# flipdotctl.net
KiCad netlist of a schematic drawn in EAGLE
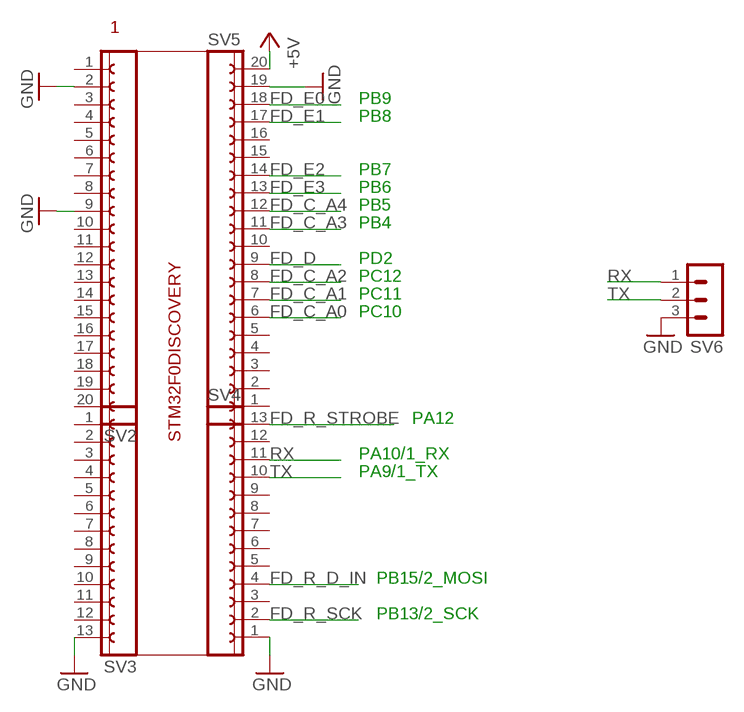
[diagram p0: schematic, sheet 1]
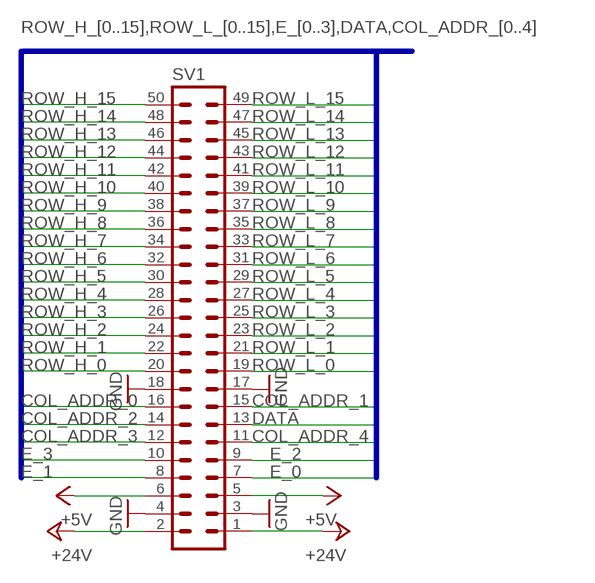
[diagram p1: schematic, sheet 2]
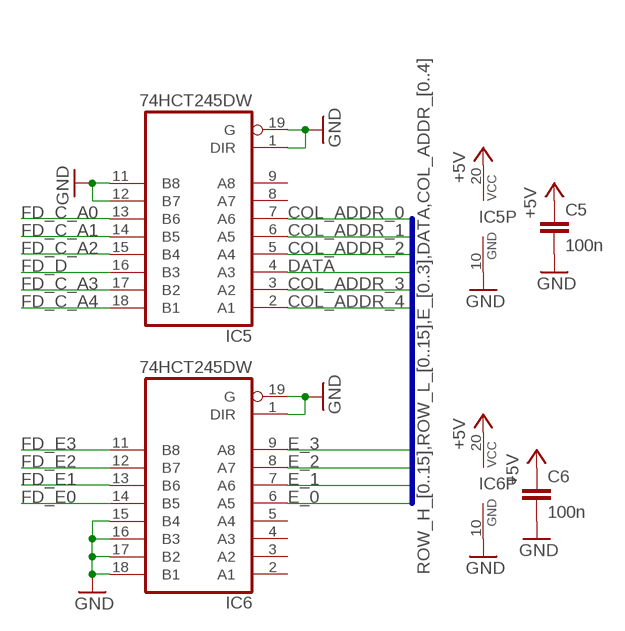
[diagram p2: schematic, sheet 3]
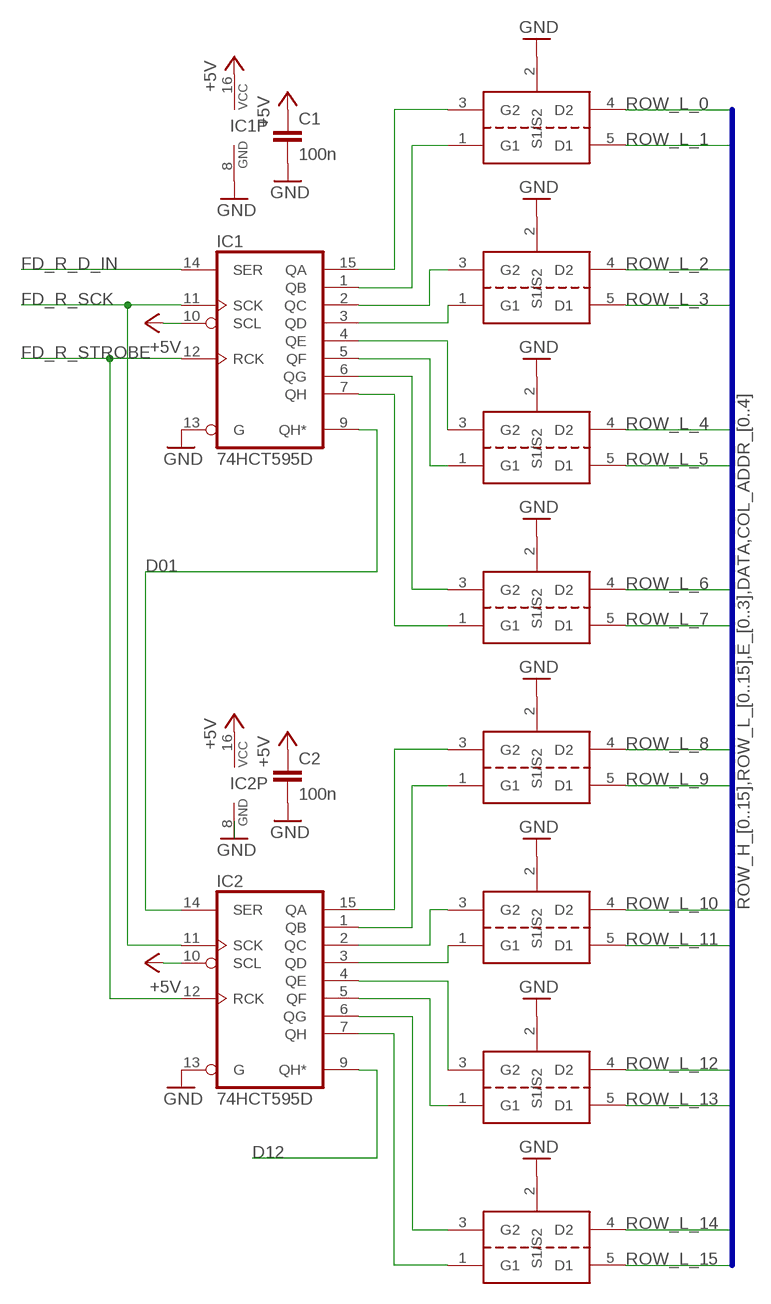
[diagram p3: schematic, sheet 4]
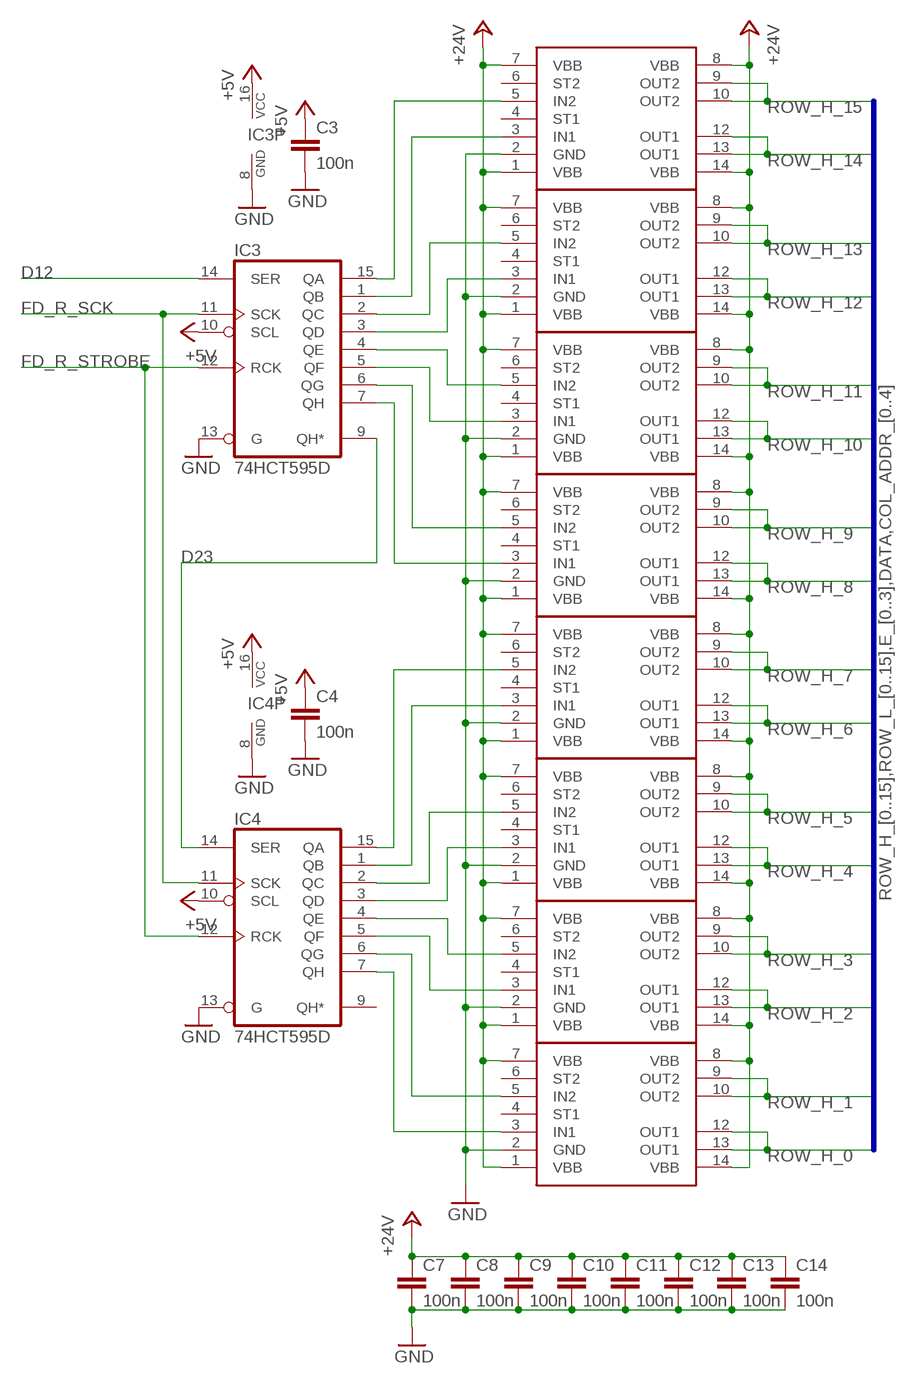
[diagram p4: schematic, sheet 5]
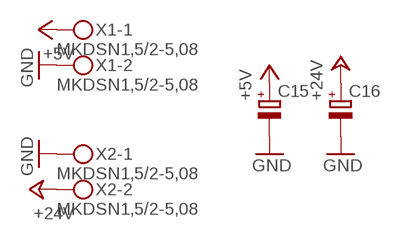
[diagram p5: schematic, sheet 6]

(export (version "E")
  (design (tool "Eeschema 10.0.6"))
  (components
    (comp (ref "C3")
      (value "100n")
      (footprint "eagle-import:C0603")
      (libsource (lib "eagle-import") (part "C-EUC0603"))
    )
    (comp (ref "C4")
      (value "100n")
      (footprint "eagle-import:C0603")
      (libsource (lib "eagle-import") (part "C-EUC0603"))
    )
    (comp (ref "C7")
      (value "100n")
      (footprint "eagle-import:C0603")
      (libsource (lib "eagle-import") (part "C-EUC0603"))
    )
    (comp (ref "C8")
      (value "100n")
      (footprint "eagle-import:C0603")
      (libsource (lib "eagle-import") (part "C-EUC0603"))
    )
    (comp (ref "C9")
      (value "100n")
      (footprint "eagle-import:C0603")
      (libsource (lib "eagle-import") (part "C-EUC0603"))
    )
    (comp (ref "C10")
      (value "100n")
      (footprint "eagle-import:C0603")
      (libsource (lib "eagle-import") (part "C-EUC0603"))
    )
    (comp (ref "C11")
      (value "100n")
      (footprint "eagle-import:C0603")
      (libsource (lib "eagle-import") (part "C-EUC0603"))
    )
    (comp (ref "C12")
      (value "100n")
      (footprint "eagle-import:C0603")
      (libsource (lib "eagle-import") (part "C-EUC0603"))
    )
    (comp (ref "C13")
      (value "100n")
      (footprint "eagle-import:C0603")
      (libsource (lib "eagle-import") (part "C-EUC0603"))
    )
    (comp (ref "C14")
      (value "100n")
      (footprint "eagle-import:C0603")
      (libsource (lib "eagle-import") (part "C-EUC0603"))
    )
    (comp (ref "IC3")
      (value "74HCT595D")
      (footprint "eagle-import:SO16")
      (libsource (lib "eagle-import") (part "74595DHCT"))
    )
    (comp (ref "IC4")
      (value "74HCT595D")
      (footprint "eagle-import:SO16")
      (libsource (lib "eagle-import") (part "74595DHCT"))
    )
    (comp (ref "U$9")
      (value "BTS5210G")
      (footprint "eagle-import:SO-14")
      (libsource (lib "eagle-import") (part "BTS5210G"))
    )
    (comp (ref "U$10")
      (value "BTS5210G")
      (footprint "eagle-import:SO-14")
      (libsource (lib "eagle-import") (part "BTS5210G"))
    )
    (comp (ref "U$11")
      (value "BTS5210G")
      (footprint "eagle-import:SO-14")
      (libsource (lib "eagle-import") (part "BTS5210G"))
    )
    (comp (ref "U$12")
      (value "BTS5210G")
      (footprint "eagle-import:SO-14")
      (libsource (lib "eagle-import") (part "BTS5210G"))
    )
    (comp (ref "U$13")
      (value "BTS5210G")
      (footprint "eagle-import:SO-14")
      (libsource (lib "eagle-import") (part "BTS5210G"))
    )
    (comp (ref "U$14")
      (value "BTS5210G")
      (footprint "eagle-import:SO-14")
      (libsource (lib "eagle-import") (part "BTS5210G"))
    )
    (comp (ref "U$15")
      (value "BTS5210G")
      (footprint "eagle-import:SO-14")
      (libsource (lib "eagle-import") (part "BTS5210G"))
    )
    (comp (ref "U$16")
      (value "BTS5210G")
      (footprint "eagle-import:SO-14")
      (libsource (lib "eagle-import") (part "BTS5210G"))
    )
    (comp (ref "SV2")
      (value "FE20-1")
      (footprint "eagle-import:FE20")
      (libsource (lib "eagle-import") (part "FE20-1"))
    )
    (comp (ref "SV3")
      (value "FE13-1")
      (footprint "eagle-import:FE13")
      (libsource (lib "eagle-import") (part "FE13-1"))
    )
    (comp (ref "SV4")
      (value "FE13-1")
      (footprint "eagle-import:FE13")
      (libsource (lib "eagle-import") (part "FE13-1"))
    )
    (comp (ref "SV5")
      (value "FE20-1")
      (footprint "eagle-import:FE20")
      (libsource (lib "eagle-import") (part "FE20-1"))
    )
    (comp (ref "SV6")
      (value "MA03-1")
      (footprint "eagle-import:MA03-1")
      (libsource (lib "eagle-import") (part "MA03-1"))
    )
    (comp (ref "C1")
      (value "100n")
      (footprint "eagle-import:C0603")
      (libsource (lib "eagle-import") (part "C-EUC0603"))
    )
    (comp (ref "C2")
      (value "100n")
      (footprint "eagle-import:C0603")
      (libsource (lib "eagle-import") (part "C-EUC0603"))
    )
    (comp (ref "IC1")
      (value "74HCT595D")
      (footprint "eagle-import:SO16")
      (libsource (lib "eagle-import") (part "74595DHCT"))
    )
    (comp (ref "IC2")
      (value "74HCT595D")
      (footprint "eagle-import:SO16")
      (libsource (lib "eagle-import") (part "74595DHCT"))
    )
    (comp (ref "U$1")
      (value "QS5K2")
      (footprint "eagle-import:SOT23-5L")
      (libsource (lib "eagle-import") (part "QS5K2"))
    )
    (comp (ref "U$2")
      (value "QS5K2")
      (footprint "eagle-import:SOT23-5L")
      (libsource (lib "eagle-import") (part "QS5K2"))
    )
    (comp (ref "U$3")
      (value "QS5K2")
      (footprint "eagle-import:SOT23-5L")
      (libsource (lib "eagle-import") (part "QS5K2"))
    )
    (comp (ref "U$4")
      (value "QS5K2")
      (footprint "eagle-import:SOT23-5L")
      (libsource (lib "eagle-import") (part "QS5K2"))
    )
    (comp (ref "U$5")
      (value "QS5K2")
      (footprint "eagle-import:SOT23-5L")
      (libsource (lib "eagle-import") (part "QS5K2"))
    )
    (comp (ref "U$6")
      (value "QS5K2")
      (footprint "eagle-import:SOT23-5L")
      (libsource (lib "eagle-import") (part "QS5K2"))
    )
    (comp (ref "U$7")
      (value "QS5K2")
      (footprint "eagle-import:SOT23-5L")
      (libsource (lib "eagle-import") (part "QS5K2"))
    )
    (comp (ref "U$8")
      (value "QS5K2")
      (footprint "eagle-import:SOT23-5L")
      (libsource (lib "eagle-import") (part "QS5K2"))
    )
    (comp (ref "SV1")
      (value "ML50")
      (footprint "eagle-import:ML50")
      (libsource (lib "eagle-import") (part "ML50"))
    )
    (comp (ref "C15")
      (value "CPOL-EUE2.5-6")
      (footprint "eagle-import:E2,5-6")
      (libsource (lib "eagle-import") (part "CPOL-EUE2.5-6"))
    )
    (comp (ref "C16")
      (value "CPOL-EUE2.5-6")
      (footprint "eagle-import:E2,5-6")
      (libsource (lib "eagle-import") (part "CPOL-EUE2.5-6"))
    )
    (comp (ref "X1")
      (value "MKDSN1,5/2-5,08")
      (footprint "eagle-import:MKDSN1,5_2-5,08")
      (fields (field (name "MPN") "MKDSN 1,5/2-5.08"))
      (libsource (lib "eagle-import") (part "MKDSN1,5/2-5,08"))
    )
    (comp (ref "X2")
      (value "MKDSN1,5/2-5,08")
      (footprint "eagle-import:MKDSN1,5_2-5,08")
      (fields (field (name "MPN") "MKDSN 1,5/2-5.08"))
      (libsource (lib "eagle-import") (part "MKDSN1,5/2-5,08"))
    )
    (comp (ref "C5")
      (value "100n")
      (footprint "eagle-import:C0603")
      (libsource (lib "eagle-import") (part "C-EUC0603"))
    )
    (comp (ref "C6")
      (value "100n")
      (footprint "eagle-import:C0603")
      (libsource (lib "eagle-import") (part "C-EUC0603"))
    )
    (comp (ref "IC5")
      (value "74HCT245DW")
      (footprint "eagle-import:SO20W")
      (libsource (lib "eagle-import") (part "74245DWHCT"))
    )
    (comp (ref "IC6")
      (value "74HCT245DW")
      (footprint "eagle-import:SO20W")
      (libsource (lib "eagle-import") (part "74245DWHCT"))
    )
  )
  (nets
    (net (code "3") (name "+5V") (class "Default")
      (node (ref "C1") (pin "1") (pinfunction "1_1") (pintype "passive"))
      (node (ref "C15") (pin "+") (pinfunction "+_+") (pintype "passive"))
      (node (ref "C2") (pin "1") (pinfunction "1_1") (pintype "passive"))
      (node (ref "C3") (pin "1") (pinfunction "1_1") (pintype "passive"))
      (node (ref "C4") (pin "1") (pinfunction "1_1") (pintype "passive"))
      (node (ref "C5") (pin "1") (pinfunction "1_1") (pintype "passive"))
      (node (ref "C6") (pin "1") (pinfunction "1_1") (pintype "passive"))
      (node (ref "IC1") (pin "10") (pinfunction "SCL_10") (pintype "input"))
      (node (ref "IC1") (pin "16") (pinfunction "VCC_16") (pintype "power_in"))
      (node (ref "IC2") (pin "10") (pinfunction "SCL_10") (pintype "input"))
      (node (ref "IC2") (pin "16") (pinfunction "VCC_16") (pintype "power_in"))
      (node (ref "IC3") (pin "10") (pinfunction "SCL_10") (pintype "input"))
      (node (ref "IC3") (pin "16") (pinfunction "VCC_16") (pintype "power_in"))
      (node (ref "IC4") (pin "10") (pinfunction "SCL_10") (pintype "input"))
      (node (ref "IC4") (pin "16") (pinfunction "VCC_16") (pintype "power_in"))
      (node (ref "IC5") (pin "20") (pinfunction "VCC_20") (pintype "power_in"))
      (node (ref "IC6") (pin "20") (pinfunction "VCC_20") (pintype "power_in"))
      (node (ref "SV1") (pin "5") (pinfunction "5_5") (pintype "passive"))
      (node (ref "SV1") (pin "6") (pinfunction "6_6") (pintype "passive"))
      (node (ref "SV5") (pin "20") (pinfunction "20_20") (pintype "passive"))
      (node (ref "X1") (pin "1") (pinfunction "KL_1") (pintype "passive"))
    )
    (net (code "4") (name "+24V") (class "Default")
      (node (ref "C10") (pin "1") (pinfunction "1_1") (pintype "passive"))
      (node (ref "C11") (pin "1") (pinfunction "1_1") (pintype "passive"))
      (node (ref "C12") (pin "1") (pinfunction "1_1") (pintype "passive"))
      (node (ref "C13") (pin "1") (pinfunction "1_1") (pintype "passive"))
      (node (ref "C14") (pin "1") (pinfunction "1_1") (pintype "passive"))
      (node (ref "C16") (pin "+") (pinfunction "+_+") (pintype "passive"))
      (node (ref "C7") (pin "1") (pinfunction "1_1") (pintype "passive"))
      (node (ref "C8") (pin "1") (pinfunction "1_1") (pintype "passive"))
      (node (ref "C9") (pin "1") (pinfunction "1_1") (pintype "passive"))
      (node (ref "SV1") (pin "1") (pinfunction "1_1") (pintype "passive"))
      (node (ref "SV1") (pin "2") (pinfunction "2_2") (pintype "passive"))
      (node (ref "U$10") (pin "1") (pinfunction "VBB_1") (pintype "bidirectional"))
      (node (ref "U$10") (pin "14") (pinfunction "VBB_14") (pintype "bidirectional"))
      (node (ref "U$10") (pin "7") (pinfunction "VBB_7") (pintype "bidirectional"))
      (node (ref "U$10") (pin "8") (pinfunction "VBB_8") (pintype "bidirectional"))
      (node (ref "U$11") (pin "1") (pinfunction "VBB_1") (pintype "bidirectional"))
      (node (ref "U$11") (pin "14") (pinfunction "VBB_14") (pintype "bidirectional"))
      (node (ref "U$11") (pin "7") (pinfunction "VBB_7") (pintype "bidirectional"))
      (node (ref "U$11") (pin "8") (pinfunction "VBB_8") (pintype "bidirectional"))
      (node (ref "U$12") (pin "1") (pinfunction "VBB_1") (pintype "bidirectional"))
      (node (ref "U$12") (pin "14") (pinfunction "VBB_14") (pintype "bidirectional"))
      (node (ref "U$12") (pin "7") (pinfunction "VBB_7") (pintype "bidirectional"))
      (node (ref "U$12") (pin "8") (pinfunction "VBB_8") (pintype "bidirectional"))
      (node (ref "U$13") (pin "1") (pinfunction "VBB_1") (pintype "bidirectional"))
      (node (ref "U$13") (pin "14") (pinfunction "VBB_14") (pintype "bidirectional"))
      (node (ref "U$13") (pin "7") (pinfunction "VBB_7") (pintype "bidirectional"))
      (node (ref "U$13") (pin "8") (pinfunction "VBB_8") (pintype "bidirectional"))
      (node (ref "U$14") (pin "1") (pinfunction "VBB_1") (pintype "bidirectional"))
      (node (ref "U$14") (pin "14") (pinfunction "VBB_14") (pintype "bidirectional"))
      (node (ref "U$14") (pin "7") (pinfunction "VBB_7") (pintype "bidirectional"))
      (node (ref "U$14") (pin "8") (pinfunction "VBB_8") (pintype "bidirectional"))
      (node (ref "U$15") (pin "1") (pinfunction "VBB_1") (pintype "bidirectional"))
      (node (ref "U$15") (pin "14") (pinfunction "VBB_14") (pintype "bidirectional"))
      (node (ref "U$15") (pin "7") (pinfunction "VBB_7") (pintype "bidirectional"))
      (node (ref "U$15") (pin "8") (pinfunction "VBB_8") (pintype "bidirectional"))
      (node (ref "U$16") (pin "1") (pinfunction "VBB_1") (pintype "bidirectional"))
      (node (ref "U$16") (pin "14") (pinfunction "VBB_14") (pintype "bidirectional"))
      (node (ref "U$16") (pin "7") (pinfunction "VBB_7") (pintype "bidirectional"))
      (node (ref "U$16") (pin "8") (pinfunction "VBB_8") (pintype "bidirectional"))
      (node (ref "U$9") (pin "1") (pinfunction "VBB_1") (pintype "bidirectional"))
      (node (ref "U$9") (pin "14") (pinfunction "VBB_14") (pintype "bidirectional"))
      (node (ref "U$9") (pin "7") (pinfunction "VBB_7") (pintype "bidirectional"))
      (node (ref "U$9") (pin "8") (pinfunction "VBB_8") (pintype "bidirectional"))
      (node (ref "X2") (pin "2") (pinfunction "KL_2") (pintype "passive"))
    )
    (net (code "9") (name "COL_ADDR_0") (class "Default")
      (node (ref "IC5") (pin "7") (pinfunction "A6_7") (pintype "bidirectional"))
      (node (ref "SV1") (pin "16") (pinfunction "16_16") (pintype "passive"))
    )
    (net (code "10") (name "COL_ADDR_1") (class "Default")
      (node (ref "IC5") (pin "6") (pinfunction "A5_6") (pintype "bidirectional"))
      (node (ref "SV1") (pin "15") (pinfunction "15_15") (pintype "passive"))
    )
    (net (code "11") (name "COL_ADDR_2") (class "Default")
      (node (ref "IC5") (pin "5") (pinfunction "A4_5") (pintype "bidirectional"))
      (node (ref "SV1") (pin "14") (pinfunction "14_14") (pintype "passive"))
    )
    (net (code "12") (name "COL_ADDR_3") (class "Default")
      (node (ref "IC5") (pin "3") (pinfunction "A2_3") (pintype "bidirectional"))
      (node (ref "SV1") (pin "12") (pinfunction "12_12") (pintype "passive"))
    )
    (net (code "13") (name "COL_ADDR_4") (class "Default")
      (node (ref "IC5") (pin "2") (pinfunction "A1_2") (pintype "bidirectional"))
      (node (ref "SV1") (pin "11") (pinfunction "11_11") (pintype "passive"))
    )
    (net (code "14") (name "D01") (class "Default")
      (node (ref "IC1") (pin "9") (pinfunction "QH*_9") (pintype "tri_state"))
      (node (ref "IC2") (pin "14") (pinfunction "SER_14") (pintype "input"))
    )
    (net (code "15") (name "D12") (class "Default")
      (node (ref "IC2") (pin "9") (pinfunction "QH*_9") (pintype "tri_state"))
      (node (ref "IC3") (pin "14") (pinfunction "SER_14") (pintype "input"))
    )
    (net (code "16") (name "D23") (class "Default")
      (node (ref "IC3") (pin "9") (pinfunction "QH*_9") (pintype "tri_state"))
      (node (ref "IC4") (pin "14") (pinfunction "SER_14") (pintype "input"))
    )
    (net (code "17") (name "DATA") (class "Default")
      (node (ref "IC5") (pin "4") (pinfunction "A3_4") (pintype "bidirectional"))
      (node (ref "SV1") (pin "13") (pinfunction "13_13") (pintype "passive"))
    )
    (net (code "18") (name "E_0") (class "Default")
      (node (ref "IC6") (pin "6") (pinfunction "A5_6") (pintype "bidirectional"))
      (node (ref "SV1") (pin "7") (pinfunction "7_7") (pintype "passive"))
    )
    (net (code "19") (name "E_1") (class "Default")
      (node (ref "IC6") (pin "7") (pinfunction "A6_7") (pintype "bidirectional"))
      (node (ref "SV1") (pin "8") (pinfunction "8_8") (pintype "passive"))
    )
    (net (code "20") (name "E_2") (class "Default")
      (node (ref "IC6") (pin "8") (pinfunction "A7_8") (pintype "bidirectional"))
      (node (ref "SV1") (pin "9") (pinfunction "9_9") (pintype "passive"))
    )
    (net (code "21") (name "E_3") (class "Default")
      (node (ref "IC6") (pin "9") (pinfunction "A8_9") (pintype "bidirectional"))
      (node (ref "SV1") (pin "10") (pinfunction "10_10") (pintype "passive"))
    )
    (net (code "22") (name "FD_C_A0") (class "Default")
      (node (ref "IC5") (pin "13") (pinfunction "B6_13") (pintype "bidirectional"))
      (node (ref "SV5") (pin "6") (pinfunction "6_6") (pintype "passive"))
    )
    (net (code "23") (name "FD_C_A1") (class "Default")
      (node (ref "IC5") (pin "14") (pinfunction "B5_14") (pintype "bidirectional"))
      (node (ref "SV5") (pin "7") (pinfunction "7_7") (pintype "passive"))
    )
    (net (code "24") (name "FD_C_A2") (class "Default")
      (node (ref "IC5") (pin "15") (pinfunction "B4_15") (pintype "bidirectional"))
      (node (ref "SV5") (pin "8") (pinfunction "8_8") (pintype "passive"))
    )
    (net (code "25") (name "FD_C_A3") (class "Default")
      (node (ref "IC5") (pin "17") (pinfunction "B2_17") (pintype "bidirectional"))
      (node (ref "SV5") (pin "11") (pinfunction "11_11") (pintype "passive"))
    )
    (net (code "26") (name "FD_C_A4") (class "Default")
      (node (ref "IC5") (pin "18") (pinfunction "B1_18") (pintype "bidirectional"))
      (node (ref "SV5") (pin "12") (pinfunction "12_12") (pintype "passive"))
    )
    (net (code "27") (name "FD_D") (class "Default")
      (node (ref "IC5") (pin "16") (pinfunction "B3_16") (pintype "bidirectional"))
      (node (ref "SV5") (pin "9") (pinfunction "9_9") (pintype "passive"))
    )
    (net (code "28") (name "FD_E0") (class "Default")
      (node (ref "IC6") (pin "14") (pinfunction "B5_14") (pintype "bidirectional"))
      (node (ref "SV5") (pin "18") (pinfunction "18_18") (pintype "passive"))
    )
    (net (code "29") (name "FD_E1") (class "Default")
      (node (ref "IC6") (pin "13") (pinfunction "B6_13") (pintype "bidirectional"))
      (node (ref "SV5") (pin "17") (pinfunction "17_17") (pintype "passive"))
    )
    (net (code "30") (name "FD_E2") (class "Default")
      (node (ref "IC6") (pin "12") (pinfunction "B7_12") (pintype "bidirectional"))
      (node (ref "SV5") (pin "14") (pinfunction "14_14") (pintype "passive"))
    )
    (net (code "31") (name "FD_E3") (class "Default")
      (node (ref "IC6") (pin "11") (pinfunction "B8_11") (pintype "bidirectional"))
      (node (ref "SV5") (pin "13") (pinfunction "13_13") (pintype "passive"))
    )
    (net (code "32") (name "FD_R_D_IN") (class "Default")
      (node (ref "IC1") (pin "14") (pinfunction "SER_14") (pintype "input"))
      (node (ref "SV4") (pin "4") (pinfunction "4_4") (pintype "passive"))
    )
    (net (code "33") (name "FD_R_SCK") (class "Default")
      (node (ref "IC1") (pin "11") (pinfunction "SCK_11") (pintype "input"))
      (node (ref "IC2") (pin "11") (pinfunction "SCK_11") (pintype "input"))
      (node (ref "IC3") (pin "11") (pinfunction "SCK_11") (pintype "input"))
      (node (ref "IC4") (pin "11") (pinfunction "SCK_11") (pintype "input"))
      (node (ref "SV4") (pin "2") (pinfunction "2_2") (pintype "passive"))
    )
    (net (code "34") (name "FD_R_STROBE") (class "Default")
      (node (ref "IC1") (pin "12") (pinfunction "RCK_12") (pintype "input"))
      (node (ref "IC2") (pin "12") (pinfunction "RCK_12") (pintype "input"))
      (node (ref "IC3") (pin "12") (pinfunction "RCK_12") (pintype "input"))
      (node (ref "IC4") (pin "12") (pinfunction "RCK_12") (pintype "input"))
      (node (ref "SV4") (pin "13") (pinfunction "13_13") (pintype "passive"))
    )
    (net (code "35") (name "GND") (class "Default")
      (node (ref "C1") (pin "2") (pinfunction "2_2") (pintype "passive"))
      (node (ref "C10") (pin "2") (pinfunction "2_2") (pintype "passive"))
      (node (ref "C11") (pin "2") (pinfunction "2_2") (pintype "passive"))
      (node (ref "C12") (pin "2") (pinfunction "2_2") (pintype "passive"))
      (node (ref "C13") (pin "2") (pinfunction "2_2") (pintype "passive"))
      (node (ref "C14") (pin "2") (pinfunction "2_2") (pintype "passive"))
      (node (ref "C15") (pin "-") (pinfunction "-_-") (pintype "passive"))
      (node (ref "C16") (pin "-") (pinfunction "-_-") (pintype "passive"))
      (node (ref "C2") (pin "2") (pinfunction "2_2") (pintype "passive"))
      (node (ref "C3") (pin "2") (pinfunction "2_2") (pintype "passive"))
      (node (ref "C4") (pin "2") (pinfunction "2_2") (pintype "passive"))
      (node (ref "C5") (pin "2") (pinfunction "2_2") (pintype "passive"))
      (node (ref "C6") (pin "2") (pinfunction "2_2") (pintype "passive"))
      (node (ref "C7") (pin "2") (pinfunction "2_2") (pintype "passive"))
      (node (ref "C8") (pin "2") (pinfunction "2_2") (pintype "passive"))
      (node (ref "C9") (pin "2") (pinfunction "2_2") (pintype "passive"))
      (node (ref "IC1") (pin "13") (pinfunction "G_13") (pintype "input"))
      (node (ref "IC1") (pin "8") (pinfunction "GND_8") (pintype "power_in"))
      (node (ref "IC2") (pin "13") (pinfunction "G_13") (pintype "input"))
      (node (ref "IC2") (pin "8") (pinfunction "GND_8") (pintype "power_in"))
      (node (ref "IC3") (pin "13") (pinfunction "G_13") (pintype "input"))
      (node (ref "IC3") (pin "8") (pinfunction "GND_8") (pintype "power_in"))
      (node (ref "IC4") (pin "13") (pinfunction "G_13") (pintype "input"))
      (node (ref "IC4") (pin "8") (pinfunction "GND_8") (pintype "power_in"))
      (node (ref "IC5") (pin "1") (pinfunction "DIR_1") (pintype "input"))
      (node (ref "IC5") (pin "10") (pinfunction "GND_10") (pintype "power_in"))
      (node (ref "IC5") (pin "11") (pinfunction "B8_11") (pintype "bidirectional"))
      (node (ref "IC5") (pin "12") (pinfunction "B7_12") (pintype "bidirectional"))
      (node (ref "IC5") (pin "19") (pinfunction "G_19") (pintype "input"))
      (node (ref "IC6") (pin "1") (pinfunction "DIR_1") (pintype "input"))
      (node (ref "IC6") (pin "10") (pinfunction "GND_10") (pintype "power_in"))
      (node (ref "IC6") (pin "15") (pinfunction "B4_15") (pintype "bidirectional"))
      (node (ref "IC6") (pin "16") (pinfunction "B3_16") (pintype "bidirectional"))
      (node (ref "IC6") (pin "17") (pinfunction "B2_17") (pintype "bidirectional"))
      (node (ref "IC6") (pin "18") (pinfunction "B1_18") (pintype "bidirectional"))
      (node (ref "IC6") (pin "19") (pinfunction "G_19") (pintype "input"))
      (node (ref "SV1") (pin "17") (pinfunction "17_17") (pintype "passive"))
      (node (ref "SV1") (pin "18") (pinfunction "18_18") (pintype "passive"))
      (node (ref "SV1") (pin "3") (pinfunction "3_3") (pintype "passive"))
      (node (ref "SV1") (pin "4") (pinfunction "4_4") (pintype "passive"))
      (node (ref "SV2") (pin "2") (pinfunction "2_2") (pintype "passive"))
      (node (ref "SV2") (pin "9") (pinfunction "9_9") (pintype "passive"))
      (node (ref "SV3") (pin "13") (pinfunction "13_13") (pintype "passive"))
      (node (ref "SV4") (pin "1") (pinfunction "1_1") (pintype "passive"))
      (node (ref "SV5") (pin "19") (pinfunction "19_19") (pintype "passive"))
      (node (ref "SV6") (pin "3") (pinfunction "3_3") (pintype "passive"))
      (node (ref "U$1") (pin "2") (pinfunction "S1/S2_2") (pintype "bidirectional"))
      (node (ref "U$10") (pin "2") (pinfunction "GND_2") (pintype "bidirectional"))
      (node (ref "U$11") (pin "2") (pinfunction "GND_2") (pintype "bidirectional"))
      (node (ref "U$12") (pin "2") (pinfunction "GND_2") (pintype "bidirectional"))
      (node (ref "U$13") (pin "2") (pinfunction "GND_2") (pintype "bidirectional"))
      (node (ref "U$14") (pin "2") (pinfunction "GND_2") (pintype "bidirectional"))
      (node (ref "U$15") (pin "2") (pinfunction "GND_2") (pintype "bidirectional"))
      (node (ref "U$16") (pin "2") (pinfunction "GND_2") (pintype "bidirectional"))
      (node (ref "U$2") (pin "2") (pinfunction "S1/S2_2") (pintype "bidirectional"))
      (node (ref "U$3") (pin "2") (pinfunction "S1/S2_2") (pintype "bidirectional"))
      (node (ref "U$4") (pin "2") (pinfunction "S1/S2_2") (pintype "bidirectional"))
      (node (ref "U$5") (pin "2") (pinfunction "S1/S2_2") (pintype "bidirectional"))
      (node (ref "U$6") (pin "2") (pinfunction "S1/S2_2") (pintype "bidirectional"))
      (node (ref "U$7") (pin "2") (pinfunction "S1/S2_2") (pintype "bidirectional"))
      (node (ref "U$8") (pin "2") (pinfunction "S1/S2_2") (pintype "bidirectional"))
      (node (ref "U$9") (pin "2") (pinfunction "GND_2") (pintype "bidirectional"))
      (node (ref "X1") (pin "2") (pinfunction "KL_2") (pintype "passive"))
      (node (ref "X2") (pin "1") (pinfunction "KL_1") (pintype "passive"))
    )
    (net (code "36") (name "Net-(IC1A-QA)") (class "Default")
      (node (ref "IC1") (pin "15") (pinfunction "QA_15") (pintype "tri_state"))
      (node (ref "U$1") (pin "3") (pinfunction "G2_3") (pintype "bidirectional"))
    )
    (net (code "37") (name "Net-(IC1A-QB)") (class "Default")
      (node (ref "IC1") (pin "1") (pinfunction "QB_1") (pintype "tri_state"))
      (node (ref "U$1") (pin "1") (pinfunction "G1_1") (pintype "bidirectional"))
    )
    (net (code "38") (name "Net-(IC1A-QC)") (class "Default")
      (node (ref "IC1") (pin "2") (pinfunction "QC_2") (pintype "tri_state"))
      (node (ref "U$2") (pin "3") (pinfunction "G2_3") (pintype "bidirectional"))
    )
    (net (code "39") (name "Net-(IC1A-QD)") (class "Default")
      (node (ref "IC1") (pin "3") (pinfunction "QD_3") (pintype "tri_state"))
      (node (ref "U$2") (pin "1") (pinfunction "G1_1") (pintype "bidirectional"))
    )
    (net (code "40") (name "Net-(IC1A-QE)") (class "Default")
      (node (ref "IC1") (pin "4") (pinfunction "QE_4") (pintype "tri_state"))
      (node (ref "U$3") (pin "3") (pinfunction "G2_3") (pintype "bidirectional"))
    )
    (net (code "41") (name "Net-(IC1A-QF)") (class "Default")
      (node (ref "IC1") (pin "5") (pinfunction "QF_5") (pintype "tri_state"))
      (node (ref "U$3") (pin "1") (pinfunction "G1_1") (pintype "bidirectional"))
    )
    (net (code "42") (name "Net-(IC1A-QG)") (class "Default")
      (node (ref "IC1") (pin "6") (pinfunction "QG_6") (pintype "tri_state"))
      (node (ref "U$4") (pin "3") (pinfunction "G2_3") (pintype "bidirectional"))
    )
    (net (code "43") (name "Net-(IC1A-QH)") (class "Default")
      (node (ref "IC1") (pin "7") (pinfunction "QH_7") (pintype "tri_state"))
      (node (ref "U$4") (pin "1") (pinfunction "G1_1") (pintype "bidirectional"))
    )
    (net (code "44") (name "Net-(IC2A-QA)") (class "Default")
      (node (ref "IC2") (pin "15") (pinfunction "QA_15") (pintype "tri_state"))
      (node (ref "U$5") (pin "3") (pinfunction "G2_3") (pintype "bidirectional"))
    )
    (net (code "45") (name "Net-(IC2A-QB)") (class "Default")
      (node (ref "IC2") (pin "1") (pinfunction "QB_1") (pintype "tri_state"))
      (node (ref "U$5") (pin "1") (pinfunction "G1_1") (pintype "bidirectional"))
    )
    (net (code "46") (name "Net-(IC2A-QC)") (class "Default")
      (node (ref "IC2") (pin "2") (pinfunction "QC_2") (pintype "tri_state"))
      (node (ref "U$6") (pin "3") (pinfunction "G2_3") (pintype "bidirectional"))
    )
    (net (code "47") (name "Net-(IC2A-QD)") (class "Default")
      (node (ref "IC2") (pin "3") (pinfunction "QD_3") (pintype "tri_state"))
      (node (ref "U$6") (pin "1") (pinfunction "G1_1") (pintype "bidirectional"))
    )
    (net (code "48") (name "Net-(IC2A-QE)") (class "Default")
      (node (ref "IC2") (pin "4") (pinfunction "QE_4") (pintype "tri_state"))
      (node (ref "U$7") (pin "3") (pinfunction "G2_3") (pintype "bidirectional"))
    )
    (net (code "49") (name "Net-(IC2A-QF)") (class "Default")
      (node (ref "IC2") (pin "5") (pinfunction "QF_5") (pintype "tri_state"))
      (node (ref "U$7") (pin "1") (pinfunction "G1_1") (pintype "bidirectional"))
    )
    (net (code "50") (name "Net-(IC2A-QG)") (class "Default")
      (node (ref "IC2") (pin "6") (pinfunction "QG_6") (pintype "tri_state"))
      (node (ref "U$8") (pin "3") (pinfunction "G2_3") (pintype "bidirectional"))
    )
    (net (code "51") (name "Net-(IC2A-QH)") (class "Default")
      (node (ref "IC2") (pin "7") (pinfunction "QH_7") (pintype "tri_state"))
      (node (ref "U$8") (pin "1") (pinfunction "G1_1") (pintype "bidirectional"))
    )
    (net (code "52") (name "Net-(IC3A-QA)") (class "Default")
      (node (ref "IC3") (pin "15") (pinfunction "QA_15") (pintype "tri_state"))
      (node (ref "U$16") (pin "5") (pinfunction "IN2_5") (pintype "bidirectional"))
    )
    (net (code "53") (name "Net-(IC3A-QB)") (class "Default")
      (node (ref "IC3") (pin "1") (pinfunction "QB_1") (pintype "tri_state"))
      (node (ref "U$16") (pin "3") (pinfunction "IN1_3") (pintype "bidirectional"))
    )
    (net (code "54") (name "Net-(IC3A-QC)") (class "Default")
      (node (ref "IC3") (pin "2") (pinfunction "QC_2") (pintype "tri_state"))
      (node (ref "U$15") (pin "5") (pinfunction "IN2_5") (pintype "bidirectional"))
    )
    (net (code "55") (name "Net-(IC3A-QD)") (class "Default")
      (node (ref "IC3") (pin "3") (pinfunction "QD_3") (pintype "tri_state"))
      (node (ref "U$15") (pin "3") (pinfunction "IN1_3") (pintype "bidirectional"))
    )
    (net (code "56") (name "Net-(IC3A-QE)") (class "Default")
      (node (ref "IC3") (pin "4") (pinfunction "QE_4") (pintype "tri_state"))
      (node (ref "U$14") (pin "5") (pinfunction "IN2_5") (pintype "bidirectional"))
    )
    (net (code "57") (name "Net-(IC3A-QF)") (class "Default")
      (node (ref "IC3") (pin "5") (pinfunction "QF_5") (pintype "tri_state"))
      (node (ref "U$14") (pin "3") (pinfunction "IN1_3") (pintype "bidirectional"))
    )
    (net (code "58") (name "Net-(IC3A-QG)") (class "Default")
      (node (ref "IC3") (pin "6") (pinfunction "QG_6") (pintype "tri_state"))
      (node (ref "U$13") (pin "5") (pinfunction "IN2_5") (pintype "bidirectional"))
    )
    (net (code "59") (name "Net-(IC3A-QH)") (class "Default")
      (node (ref "IC3") (pin "7") (pinfunction "QH_7") (pintype "tri_state"))
      (node (ref "U$13") (pin "3") (pinfunction "IN1_3") (pintype "bidirectional"))
    )
    (net (code "60") (name "Net-(IC4A-QA)") (class "Default")
      (node (ref "IC4") (pin "15") (pinfunction "QA_15") (pintype "tri_state"))
      (node (ref "U$12") (pin "5") (pinfunction "IN2_5") (pintype "bidirectional"))
    )
    (net (code "61") (name "Net-(IC4A-QB)") (class "Default")
      (node (ref "IC4") (pin "1") (pinfunction "QB_1") (pintype "tri_state"))
      (node (ref "U$12") (pin "3") (pinfunction "IN1_3") (pintype "bidirectional"))
    )
    (net (code "62") (name "Net-(IC4A-QC)") (class "Default")
      (node (ref "IC4") (pin "2") (pinfunction "QC_2") (pintype "tri_state"))
      (node (ref "U$11") (pin "5") (pinfunction "IN2_5") (pintype "bidirectional"))
    )
    (net (code "63") (name "Net-(IC4A-QD)") (class "Default")
      (node (ref "IC4") (pin "3") (pinfunction "QD_3") (pintype "tri_state"))
      (node (ref "U$11") (pin "3") (pinfunction "IN1_3") (pintype "bidirectional"))
    )
    (net (code "64") (name "Net-(IC4A-QE)") (class "Default")
      (node (ref "IC4") (pin "4") (pinfunction "QE_4") (pintype "tri_state"))
      (node (ref "U$10") (pin "5") (pinfunction "IN2_5") (pintype "bidirectional"))
    )
    (net (code "65") (name "Net-(IC4A-QF)") (class "Default")
      (node (ref "IC4") (pin "5") (pinfunction "QF_5") (pintype "tri_state"))
      (node (ref "U$10") (pin "3") (pinfunction "IN1_3") (pintype "bidirectional"))
    )
    (net (code "66") (name "Net-(IC4A-QG)") (class "Default")
      (node (ref "IC4") (pin "6") (pinfunction "QG_6") (pintype "tri_state"))
      (node (ref "U$9") (pin "5") (pinfunction "IN2_5") (pintype "bidirectional"))
    )
    (net (code "67") (name "Net-(IC4A-QH)") (class "Default")
      (node (ref "IC4") (pin "7") (pinfunction "QH_7") (pintype "tri_state"))
      (node (ref "U$9") (pin "3") (pinfunction "IN1_3") (pintype "bidirectional"))
    )
    (net (code "68") (name "ROW_H_0") (class "Default")
      (node (ref "SV1") (pin "20") (pinfunction "20_20") (pintype "passive"))
      (node (ref "U$9") (pin "12") (pinfunction "OUT1_12") (pintype "bidirectional"))
      (node (ref "U$9") (pin "13") (pinfunction "OUT1_13") (pintype "bidirectional"))
    )
    (net (code "69") (name "ROW_H_1") (class "Default")
      (node (ref "SV1") (pin "22") (pinfunction "22_22") (pintype "passive"))
      (node (ref "U$9") (pin "10") (pinfunction "OUT2_10") (pintype "bidirectional"))
      (node (ref "U$9") (pin "9") (pinfunction "OUT2_9") (pintype "bidirectional"))
    )
    (net (code "70") (name "ROW_H_2") (class "Default")
      (node (ref "SV1") (pin "24") (pinfunction "24_24") (pintype "passive"))
      (node (ref "U$10") (pin "12") (pinfunction "OUT1_12") (pintype "bidirectional"))
      (node (ref "U$10") (pin "13") (pinfunction "OUT1_13") (pintype "bidirectional"))
    )
    (net (code "71") (name "ROW_H_3") (class "Default")
      (node (ref "SV1") (pin "26") (pinfunction "26_26") (pintype "passive"))
      (node (ref "U$10") (pin "10") (pinfunction "OUT2_10") (pintype "bidirectional"))
      (node (ref "U$10") (pin "9") (pinfunction "OUT2_9") (pintype "bidirectional"))
    )
    (net (code "72") (name "ROW_H_4") (class "Default")
      (node (ref "SV1") (pin "28") (pinfunction "28_28") (pintype "passive"))
      (node (ref "U$11") (pin "12") (pinfunction "OUT1_12") (pintype "bidirectional"))
      (node (ref "U$11") (pin "13") (pinfunction "OUT1_13") (pintype "bidirectional"))
    )
    (net (code "73") (name "ROW_H_5") (class "Default")
      (node (ref "SV1") (pin "30") (pinfunction "30_30") (pintype "passive"))
      (node (ref "U$11") (pin "10") (pinfunction "OUT2_10") (pintype "bidirectional"))
      (node (ref "U$11") (pin "9") (pinfunction "OUT2_9") (pintype "bidirectional"))
    )
    (net (code "74") (name "ROW_H_6") (class "Default")
      (node (ref "SV1") (pin "32") (pinfunction "32_32") (pintype "passive"))
      (node (ref "U$12") (pin "12") (pinfunction "OUT1_12") (pintype "bidirectional"))
      (node (ref "U$12") (pin "13") (pinfunction "OUT1_13") (pintype "bidirectional"))
    )
    (net (code "75") (name "ROW_H_7") (class "Default")
      (node (ref "SV1") (pin "34") (pinfunction "34_34") (pintype "passive"))
      (node (ref "U$12") (pin "10") (pinfunction "OUT2_10") (pintype "bidirectional"))
      (node (ref "U$12") (pin "9") (pinfunction "OUT2_9") (pintype "bidirectional"))
    )
    (net (code "76") (name "ROW_H_8") (class "Default")
      (node (ref "SV1") (pin "36") (pinfunction "36_36") (pintype "passive"))
      (node (ref "U$13") (pin "12") (pinfunction "OUT1_12") (pintype "bidirectional"))
      (node (ref "U$13") (pin "13") (pinfunction "OUT1_13") (pintype "bidirectional"))
    )
    (net (code "77") (name "ROW_H_9") (class "Default")
      (node (ref "SV1") (pin "38") (pinfunction "38_38") (pintype "passive"))
      (node (ref "U$13") (pin "10") (pinfunction "OUT2_10") (pintype "bidirectional"))
      (node (ref "U$13") (pin "9") (pinfunction "OUT2_9") (pintype "bidirectional"))
    )
    (net (code "78") (name "ROW_H_10") (class "Default")
      (node (ref "SV1") (pin "40") (pinfunction "40_40") (pintype "passive"))
      (node (ref "U$14") (pin "12") (pinfunction "OUT1_12") (pintype "bidirectional"))
      (node (ref "U$14") (pin "13") (pinfunction "OUT1_13") (pintype "bidirectional"))
    )
    (net (code "79") (name "ROW_H_11") (class "Default")
      (node (ref "SV1") (pin "42") (pinfunction "42_42") (pintype "passive"))
      (node (ref "U$14") (pin "10") (pinfunction "OUT2_10") (pintype "bidirectional"))
      (node (ref "U$14") (pin "9") (pinfunction "OUT2_9") (pintype "bidirectional"))
    )
    (net (code "80") (name "ROW_H_12") (class "Default")
      (node (ref "SV1") (pin "44") (pinfunction "44_44") (pintype "passive"))
      (node (ref "U$15") (pin "12") (pinfunction "OUT1_12") (pintype "bidirectional"))
      (node (ref "U$15") (pin "13") (pinfunction "OUT1_13") (pintype "bidirectional"))
    )
    (net (code "81") (name "ROW_H_13") (class "Default")
      (node (ref "SV1") (pin "46") (pinfunction "46_46") (pintype "passive"))
      (node (ref "U$15") (pin "10") (pinfunction "OUT2_10") (pintype "bidirectional"))
      (node (ref "U$15") (pin "9") (pinfunction "OUT2_9") (pintype "bidirectional"))
    )
    (net (code "82") (name "ROW_H_14") (class "Default")
      (node (ref "SV1") (pin "48") (pinfunction "48_48") (pintype "passive"))
      (node (ref "U$16") (pin "12") (pinfunction "OUT1_12") (pintype "bidirectional"))
      (node (ref "U$16") (pin "13") (pinfunction "OUT1_13") (pintype "bidirectional"))
    )
    (net (code "83") (name "ROW_H_15") (class "Default")
      (node (ref "SV1") (pin "50") (pinfunction "50_50") (pintype "passive"))
      (node (ref "U$16") (pin "10") (pinfunction "OUT2_10") (pintype "bidirectional"))
      (node (ref "U$16") (pin "9") (pinfunction "OUT2_9") (pintype "bidirectional"))
    )
    (net (code "84") (name "ROW_L_0") (class "Default")
      (node (ref "SV1") (pin "19") (pinfunction "19_19") (pintype "passive"))
      (node (ref "U$1") (pin "4") (pinfunction "D2_4") (pintype "bidirectional"))
    )
    (net (code "85") (name "ROW_L_1") (class "Default")
      (node (ref "SV1") (pin "21") (pinfunction "21_21") (pintype "passive"))
      (node (ref "U$1") (pin "5") (pinfunction "D1_5") (pintype "bidirectional"))
    )
    (net (code "86") (name "ROW_L_2") (class "Default")
      (node (ref "SV1") (pin "23") (pinfunction "23_23") (pintype "passive"))
      (node (ref "U$2") (pin "4") (pinfunction "D2_4") (pintype "bidirectional"))
    )
    (net (code "87") (name "ROW_L_3") (class "Default")
      (node (ref "SV1") (pin "25") (pinfunction "25_25") (pintype "passive"))
      (node (ref "U$2") (pin "5") (pinfunction "D1_5") (pintype "bidirectional"))
    )
    (net (code "88") (name "ROW_L_4") (class "Default")
      (node (ref "SV1") (pin "27") (pinfunction "27_27") (pintype "passive"))
      (node (ref "U$3") (pin "4") (pinfunction "D2_4") (pintype "bidirectional"))
    )
    (net (code "89") (name "ROW_L_5") (class "Default")
      (node (ref "SV1") (pin "29") (pinfunction "29_29") (pintype "passive"))
      (node (ref "U$3") (pin "5") (pinfunction "D1_5") (pintype "bidirectional"))
    )
    (net (code "90") (name "ROW_L_6") (class "Default")
      (node (ref "SV1") (pin "31") (pinfunction "31_31") (pintype "passive"))
      (node (ref "U$4") (pin "4") (pinfunction "D2_4") (pintype "bidirectional"))
    )
    (net (code "91") (name "ROW_L_7") (class "Default")
      (node (ref "SV1") (pin "33") (pinfunction "33_33") (pintype "passive"))
      (node (ref "U$4") (pin "5") (pinfunction "D1_5") (pintype "bidirectional"))
    )
    (net (code "92") (name "ROW_L_8") (class "Default")
      (node (ref "SV1") (pin "35") (pinfunction "35_35") (pintype "passive"))
      (node (ref "U$5") (pin "4") (pinfunction "D2_4") (pintype "bidirectional"))
    )
    (net (code "93") (name "ROW_L_9") (class "Default")
      (node (ref "SV1") (pin "37") (pinfunction "37_37") (pintype "passive"))
      (node (ref "U$5") (pin "5") (pinfunction "D1_5") (pintype "bidirectional"))
    )
    (net (code "94") (name "ROW_L_10") (class "Default")
      (node (ref "SV1") (pin "39") (pinfunction "39_39") (pintype "passive"))
      (node (ref "U$6") (pin "4") (pinfunction "D2_4") (pintype "bidirectional"))
    )
    (net (code "95") (name "ROW_L_11") (class "Default")
      (node (ref "SV1") (pin "41") (pinfunction "41_41") (pintype "passive"))
      (node (ref "U$6") (pin "5") (pinfunction "D1_5") (pintype "bidirectional"))
    )
    (net (code "96") (name "ROW_L_12") (class "Default")
      (node (ref "SV1") (pin "43") (pinfunction "43_43") (pintype "passive"))
      (node (ref "U$7") (pin "4") (pinfunction "D2_4") (pintype "bidirectional"))
    )
    (net (code "97") (name "ROW_L_13") (class "Default")
      (node (ref "SV1") (pin "45") (pinfunction "45_45") (pintype "passive"))
      (node (ref "U$7") (pin "5") (pinfunction "D1_5") (pintype "bidirectional"))
    )
    (net (code "98") (name "ROW_L_14") (class "Default")
      (node (ref "SV1") (pin "47") (pinfunction "47_47") (pintype "passive"))
      (node (ref "U$8") (pin "4") (pinfunction "D2_4") (pintype "bidirectional"))
    )
    (net (code "99") (name "ROW_L_15") (class "Default")
      (node (ref "SV1") (pin "49") (pinfunction "49_49") (pintype "passive"))
      (node (ref "U$8") (pin "5") (pinfunction "D1_5") (pintype "bidirectional"))
    )
    (net (code "100") (name "RX") (class "Default")
      (node (ref "SV4") (pin "11") (pinfunction "11_11") (pintype "passive"))
      (node (ref "SV6") (pin "1") (pinfunction "1_1") (pintype "passive"))
    )
    (net (code "101") (name "TX") (class "Default")
      (node (ref "SV4") (pin "10") (pinfunction "10_10") (pintype "passive"))
      (node (ref "SV6") (pin "2") (pinfunction "2_2") (pintype "passive"))
    )
    (net (code "102") (name "unconnected-(IC4A-QH*-Pad9)") (class "Default")
      (node (ref "IC4") (pin "9") (pinfunction "QH*_9") (pintype "tri_state"))
    )
    (net (code "103") (name "unconnected-(IC5A-A7-Pad8)") (class "Default")
      (node (ref "IC5") (pin "8") (pinfunction "A7_8") (pintype "bidirectional"))
    )
    (net (code "104") (name "unconnected-(IC5A-A8-Pad9)") (class "Default")
      (node (ref "IC5") (pin "9") (pinfunction "A8_9") (pintype "bidirectional"))
    )
    (net (code "105") (name "unconnected-(IC6A-A1-Pad2)") (class "Default")
      (node (ref "IC6") (pin "2") (pinfunction "A1_2") (pintype "bidirectional"))
    )
    (net (code "106") (name "unconnected-(IC6A-A2-Pad3)") (class "Default")
      (node (ref "IC6") (pin "3") (pinfunction "A2_3") (pintype "bidirectional"))
    )
    (net (code "107") (name "unconnected-(IC6A-A3-Pad4)") (class "Default")
      (node (ref "IC6") (pin "4") (pinfunction "A3_4") (pintype "bidirectional"))
    )
    (net (code "108") (name "unconnected-(IC6A-A4-Pad5)") (class "Default")
      (node (ref "IC6") (pin "5") (pinfunction "A4_5") (pintype "bidirectional"))
    )
    (net (code "109") (name "unconnected-(SV2-Pad1)") (class "Default")
      (node (ref "SV2") (pin "1") (pinfunction "1_1") (pintype "passive"))
    )
    (net (code "110") (name "unconnected-(SV2-Pad3)") (class "Default")
      (node (ref "SV2") (pin "3") (pinfunction "3_3") (pintype "passive"))
    )
    (net (code "111") (name "unconnected-(SV2-Pad4)") (class "Default")
      (node (ref "SV2") (pin "4") (pinfunction "4_4") (pintype "passive"))
    )
    (net (code "112") (name "unconnected-(SV2-Pad5)") (class "Default")
      (node (ref "SV2") (pin "5") (pinfunction "5_5") (pintype "passive"))
    )
    (net (code "113") (name "unconnected-(SV2-Pad6)") (class "Default")
      (node (ref "SV2") (pin "6") (pinfunction "6_6") (pintype "passive"))
    )
    (net (code "114") (name "unconnected-(SV2-Pad7)") (class "Default")
      (node (ref "SV2") (pin "7") (pinfunction "7_7") (pintype "passive"))
    )
    (net (code "115") (name "unconnected-(SV2-Pad8)") (class "Default")
      (node (ref "SV2") (pin "8") (pinfunction "8_8") (pintype "passive"))
    )
    (net (code "116") (name "unconnected-(SV2-Pad10)") (class "Default")
      (node (ref "SV2") (pin "10") (pinfunction "10_10") (pintype "passive"))
    )
    (net (code "117") (name "unconnected-(SV2-Pad11)") (class "Default")
      (node (ref "SV2") (pin "11") (pinfunction "11_11") (pintype "passive"))
    )
    (net (code "118") (name "unconnected-(SV2-Pad12)") (class "Default")
      (node (ref "SV2") (pin "12") (pinfunction "12_12") (pintype "passive"))
    )
    (net (code "119") (name "unconnected-(SV2-Pad13)") (class "Default")
      (node (ref "SV2") (pin "13") (pinfunction "13_13") (pintype "passive"))
    )
    (net (code "120") (name "unconnected-(SV2-Pad14)") (class "Default")
      (node (ref "SV2") (pin "14") (pinfunction "14_14") (pintype "passive"))
    )
    (net (code "121") (name "unconnected-(SV2-Pad15)") (class "Default")
      (node (ref "SV2") (pin "15") (pinfunction "15_15") (pintype "passive"))
    )
    (net (code "122") (name "unconnected-(SV2-Pad16)") (class "Default")
      (node (ref "SV2") (pin "16") (pinfunction "16_16") (pintype "passive"))
    )
    (net (code "123") (name "unconnected-(SV2-Pad17)") (class "Default")
      (node (ref "SV2") (pin "17") (pinfunction "17_17") (pintype "passive"))
    )
    (net (code "124") (name "unconnected-(SV2-Pad18)") (class "Default")
      (node (ref "SV2") (pin "18") (pinfunction "18_18") (pintype "passive"))
    )
    (net (code "125") (name "unconnected-(SV2-Pad19)") (class "Default")
      (node (ref "SV2") (pin "19") (pinfunction "19_19") (pintype "passive"))
    )
    (net (code "126") (name "unconnected-(SV2-Pad20)") (class "Default")
      (node (ref "SV2") (pin "20") (pinfunction "20_20") (pintype "passive"))
    )
    (net (code "127") (name "unconnected-(SV3-Pad1)") (class "Default")
      (node (ref "SV3") (pin "1") (pinfunction "1_1") (pintype "passive"))
    )
    (net (code "128") (name "unconnected-(SV3-Pad2)") (class "Default")
      (node (ref "SV3") (pin "2") (pinfunction "2_2") (pintype "passive"))
    )
    (net (code "129") (name "unconnected-(SV3-Pad3)") (class "Default")
      (node (ref "SV3") (pin "3") (pinfunction "3_3") (pintype "passive"))
    )
    (net (code "130") (name "unconnected-(SV3-Pad4)") (class "Default")
      (node (ref "SV3") (pin "4") (pinfunction "4_4") (pintype "passive"))
    )
    (net (code "131") (name "unconnected-(SV3-Pad5)") (class "Default")
      (node (ref "SV3") (pin "5") (pinfunction "5_5") (pintype "passive"))
    )
    (net (code "132") (name "unconnected-(SV3-Pad6)") (class "Default")
      (node (ref "SV3") (pin "6") (pinfunction "6_6") (pintype "passive"))
    )
    (net (code "133") (name "unconnected-(SV3-Pad7)") (class "Default")
      (node (ref "SV3") (pin "7") (pinfunction "7_7") (pintype "passive"))
    )
    (net (code "134") (name "unconnected-(SV3-Pad8)") (class "Default")
      (node (ref "SV3") (pin "8") (pinfunction "8_8") (pintype "passive"))
    )
    (net (code "135") (name "unconnected-(SV3-Pad9)") (class "Default")
      (node (ref "SV3") (pin "9") (pinfunction "9_9") (pintype "passive"))
    )
    (net (code "136") (name "unconnected-(SV3-Pad10)") (class "Default")
      (node (ref "SV3") (pin "10") (pinfunction "10_10") (pintype "passive"))
    )
    (net (code "137") (name "unconnected-(SV3-Pad11)") (class "Default")
      (node (ref "SV3") (pin "11") (pinfunction "11_11") (pintype "passive"))
    )
    (net (code "138") (name "unconnected-(SV3-Pad12)") (class "Default")
      (node (ref "SV3") (pin "12") (pinfunction "12_12") (pintype "passive"))
    )
    (net (code "139") (name "unconnected-(SV4-Pad3)") (class "Default")
      (node (ref "SV4") (pin "3") (pinfunction "3_3") (pintype "passive"))
    )
    (net (code "140") (name "unconnected-(SV4-Pad5)") (class "Default")
      (node (ref "SV4") (pin "5") (pinfunction "5_5") (pintype "passive"))
    )
    (net (code "141") (name "unconnected-(SV4-Pad6)") (class "Default")
      (node (ref "SV4") (pin "6") (pinfunction "6_6") (pintype "passive"))
    )
    (net (code "142") (name "unconnected-(SV4-Pad7)") (class "Default")
      (node (ref "SV4") (pin "7") (pinfunction "7_7") (pintype "passive"))
    )
    (net (code "143") (name "unconnected-(SV4-Pad8)") (class "Default")
      (node (ref "SV4") (pin "8") (pinfunction "8_8") (pintype "passive"))
    )
    (net (code "144") (name "unconnected-(SV4-Pad9)") (class "Default")
      (node (ref "SV4") (pin "9") (pinfunction "9_9") (pintype "passive"))
    )
    (net (code "145") (name "unconnected-(SV4-Pad12)") (class "Default")
      (node (ref "SV4") (pin "12") (pinfunction "12_12") (pintype "passive"))
    )
    (net (code "146") (name "unconnected-(SV5-Pad1)") (class "Default")
      (node (ref "SV5") (pin "1") (pinfunction "1_1") (pintype "passive"))
    )
    (net (code "147") (name "unconnected-(SV5-Pad2)") (class "Default")
      (node (ref "SV5") (pin "2") (pinfunction "2_2") (pintype "passive"))
    )
    (net (code "148") (name "unconnected-(SV5-Pad3)") (class "Default")
      (node (ref "SV5") (pin "3") (pinfunction "3_3") (pintype "passive"))
    )
    (net (code "149") (name "unconnected-(SV5-Pad4)") (class "Default")
      (node (ref "SV5") (pin "4") (pinfunction "4_4") (pintype "passive"))
    )
    (net (code "150") (name "unconnected-(SV5-Pad5)") (class "Default")
      (node (ref "SV5") (pin "5") (pinfunction "5_5") (pintype "passive"))
    )
    (net (code "151") (name "unconnected-(SV5-Pad10)") (class "Default")
      (node (ref "SV5") (pin "10") (pinfunction "10_10") (pintype "passive"))
    )
    (net (code "152") (name "unconnected-(SV5-Pad15)") (class "Default")
      (node (ref "SV5") (pin "15") (pinfunction "15_15") (pintype "passive"))
    )
    (net (code "153") (name "unconnected-(SV5-Pad16)") (class "Default")
      (node (ref "SV5") (pin "16") (pinfunction "16_16") (pintype "passive"))
    )
    (net (code "154") (name "unconnected-(U$9-ST1-Pad4)") (class "Default")
      (node (ref "U$9") (pin "4") (pinfunction "ST1_4") (pintype "bidirectional"))
    )
    (net (code "155") (name "unconnected-(U$9-ST2-Pad6)") (class "Default")
      (node (ref "U$9") (pin "6") (pinfunction "ST2_6") (pintype "bidirectional"))
    )
    (net (code "156") (name "unconnected-(U$10-ST1-Pad4)") (class "Default")
      (node (ref "U$10") (pin "4") (pinfunction "ST1_4") (pintype "bidirectional"))
    )
    (net (code "157") (name "unconnected-(U$10-ST2-Pad6)") (class "Default")
      (node (ref "U$10") (pin "6") (pinfunction "ST2_6") (pintype "bidirectional"))
    )
    (net (code "158") (name "unconnected-(U$11-ST1-Pad4)") (class "Default")
      (node (ref "U$11") (pin "4") (pinfunction "ST1_4") (pintype "bidirectional"))
    )
    (net (code "159") (name "unconnected-(U$11-ST2-Pad6)") (class "Default")
      (node (ref "U$11") (pin "6") (pinfunction "ST2_6") (pintype "bidirectional"))
    )
    (net (code "160") (name "unconnected-(U$12-ST1-Pad4)") (class "Default")
      (node (ref "U$12") (pin "4") (pinfunction "ST1_4") (pintype "bidirectional"))
    )
    (net (code "161") (name "unconnected-(U$12-ST2-Pad6)") (class "Default")
      (node (ref "U$12") (pin "6") (pinfunction "ST2_6") (pintype "bidirectional"))
    )
    (net (code "162") (name "unconnected-(U$13-ST1-Pad4)") (class "Default")
      (node (ref "U$13") (pin "4") (pinfunction "ST1_4") (pintype "bidirectional"))
    )
    (net (code "163") (name "unconnected-(U$13-ST2-Pad6)") (class "Default")
      (node (ref "U$13") (pin "6") (pinfunction "ST2_6") (pintype "bidirectional"))
    )
    (net (code "164") (name "unconnected-(U$14-ST1-Pad4)") (class "Default")
      (node (ref "U$14") (pin "4") (pinfunction "ST1_4") (pintype "bidirectional"))
    )
    (net (code "165") (name "unconnected-(U$14-ST2-Pad6)") (class "Default")
      (node (ref "U$14") (pin "6") (pinfunction "ST2_6") (pintype "bidirectional"))
    )
    (net (code "166") (name "unconnected-(U$15-ST1-Pad4)") (class "Default")
      (node (ref "U$15") (pin "4") (pinfunction "ST1_4") (pintype "bidirectional"))
    )
    (net (code "167") (name "unconnected-(U$15-ST2-Pad6)") (class "Default")
      (node (ref "U$15") (pin "6") (pinfunction "ST2_6") (pintype "bidirectional"))
    )
    (net (code "168") (name "unconnected-(U$16-ST1-Pad4)") (class "Default")
      (node (ref "U$16") (pin "4") (pinfunction "ST1_4") (pintype "bidirectional"))
    )
    (net (code "169") (name "unconnected-(U$16-ST2-Pad6)") (class "Default")
      (node (ref "U$16") (pin "6") (pinfunction "ST2_6") (pintype "bidirectional"))
    )
  )
)
